# Relay_Driver_V1_1.net
KiCad netlist of a schematic drawn in EAGLE
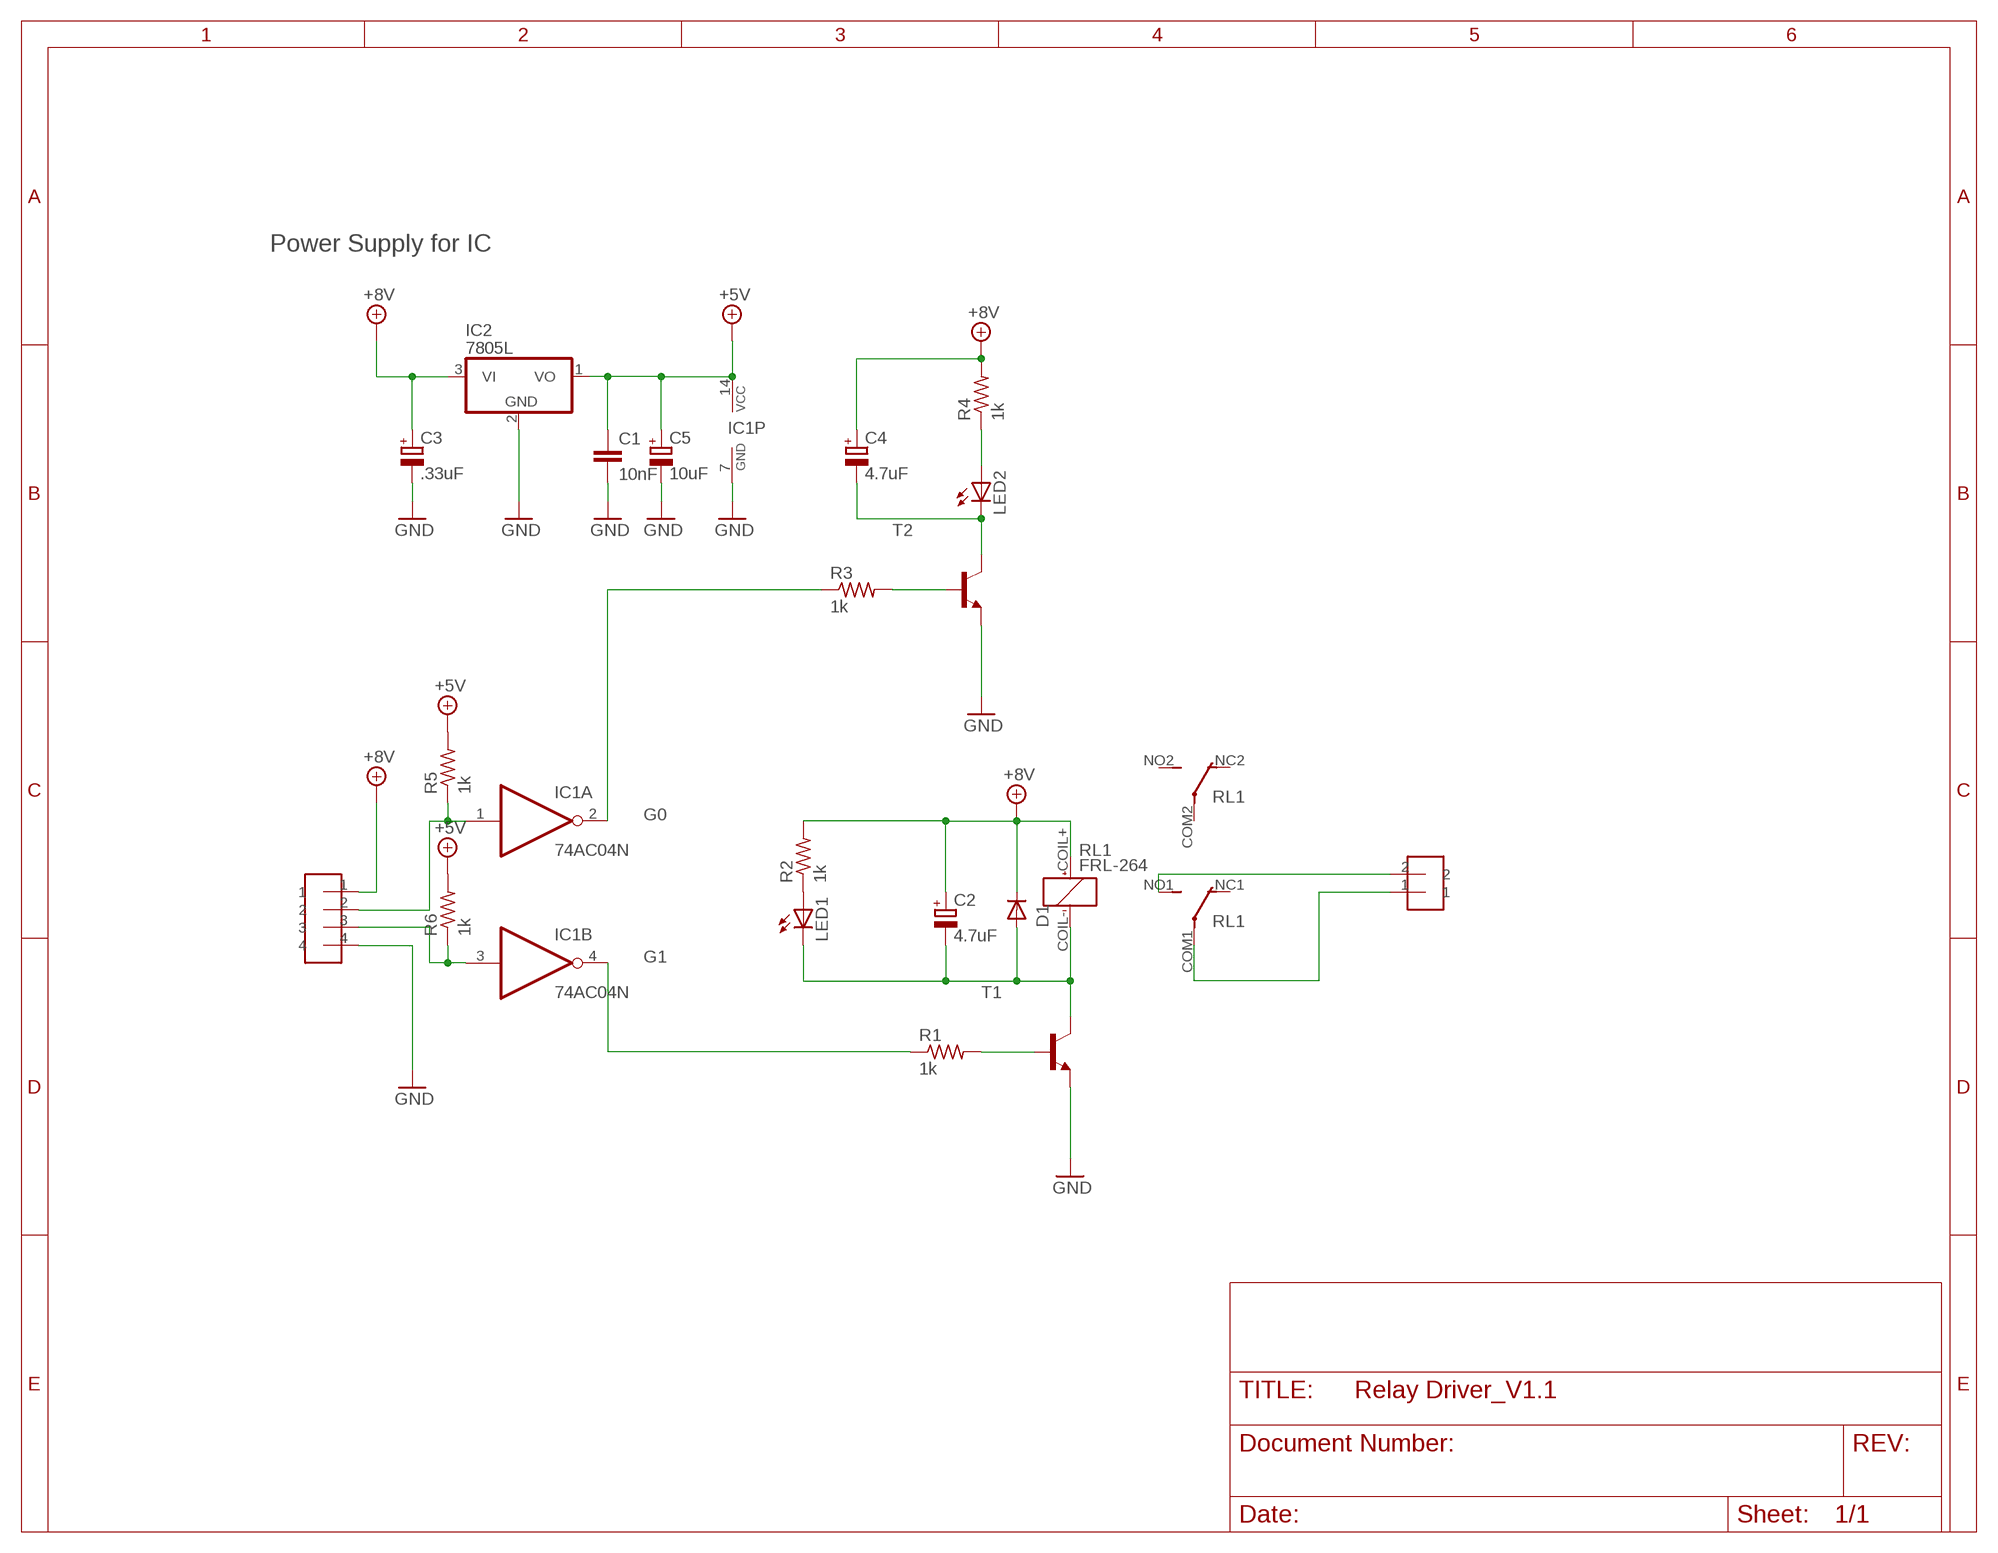
[diagram p0: schematic, sheet 1]

(export (version "E")
  (design (tool "Eeschema 10.0.6"))
  (components
    (comp (ref "C1")
      (value "10nF")
      (footprint "eagle-import:C075-042X103")
      (libsource (lib "eagle-import") (part "C-EU075-042X103"))
    )
    (comp (ref "C2")
      (value "4.7uF")
      (footprint "eagle-import:E3,5-10")
      (libsource (lib "eagle-import") (part "CPOL-EUE3.5-10"))
    )
    (comp (ref "C3")
      (value ".33uF")
      (footprint "eagle-import:E3,5-10")
      (libsource (lib "eagle-import") (part "CPOL-EUE3.5-10"))
    )
    (comp (ref "C4")
      (value "4.7uF")
      (footprint "eagle-import:E3,5-10")
      (libsource (lib "eagle-import") (part "CPOL-EUE3.5-10"))
    )
    (comp (ref "C5")
      (value "10uF")
      (footprint "eagle-import:E3,5-10")
      (libsource (lib "eagle-import") (part "CPOL-EUE3.5-10"))
    )
    (comp (ref "D1")
      (value "1N4148DO35-10")
      (footprint "eagle-import:DO35-10")
      (libsource (lib "eagle-import") (part "1N4148DO35-10"))
    )
    (comp (ref "IC1")
      (value "74AC04N")
      (footprint "eagle-import:DIL14")
      (libsource (lib "eagle-import") (part "7404NAC"))
    )
    (comp (ref "IC2")
      (value "7805L")
      (footprint "eagle-import:TO92")
      (libsource (lib "eagle-import") (part "78L05"))
    )
    (comp (ref "LED1")
      (value "LED5MM")
      (footprint "eagle-import:LED5MM")
      (libsource (lib "eagle-import") (part "LED5MM"))
    )
    (comp (ref "LED2")
      (value "LED5MM")
      (footprint "eagle-import:LED5MM")
      (libsource (lib "eagle-import") (part "LED5MM"))
    )
    (comp (ref "R1")
      (value "1k")
      (footprint "eagle-import:P0613V")
      (libsource (lib "eagle-import") (part "R-US_0613/5V"))
    )
    (comp (ref "R2")
      (value "1k")
      (footprint "eagle-import:P0613V")
      (libsource (lib "eagle-import") (part "R-US_0613/5V"))
    )
    (comp (ref "R3")
      (value "1k")
      (footprint "eagle-import:P0613V")
      (libsource (lib "eagle-import") (part "R-US_0613/5V"))
    )
    (comp (ref "R4")
      (value "1k")
      (footprint "eagle-import:P0613V")
      (libsource (lib "eagle-import") (part "R-US_0613/5V"))
    )
    (comp (ref "R5")
      (value "1k")
      (footprint "eagle-import:P0613V")
      (libsource (lib "eagle-import") (part "R-US_0613/5V"))
    )
    (comp (ref "R6")
      (value "1k")
      (footprint "eagle-import:P0613V")
      (libsource (lib "eagle-import") (part "R-US_0613/5V"))
    )
    (comp (ref "RL1")
      (value "FRL-264")
      (footprint "eagle-import:FRL-264")
      (libsource (lib "eagle-import") (part "FRL-264"))
    )
    (comp (ref "T1")
      (value "-NPN-TO92-EBC")
      (footprint "eagle-import:TO92-EBC")
      (libsource (lib "eagle-import") (part "-NPN-TO92-EBC"))
    )
    (comp (ref "T2")
      (value "-NPN-TO92-EBC")
      (footprint "eagle-import:TO92-EBC")
      (libsource (lib "eagle-import") (part "-NPN-TO92-EBC"))
    )
    (comp (ref "U$1")
      (value "1X4HEADER_100MIL")
      (footprint "eagle-import:1X4_100MIL")
      (libsource (lib "eagle-import") (part "1X4HEADER_100MIL"))
    )
    (comp (ref "U$2")
      (value "1X2HEADER_100MIL")
      (footprint "eagle-import:1X2_100MIL")
      (libsource (lib "eagle-import") (part "1X2HEADER_100MIL"))
    )
  )
  (nets
    (net (code "1") (name "+5V") (class "Default")
      (node (ref "C1") (pin "1") (pinfunction "1_1") (pintype "passive"))
      (node (ref "C5") (pin "+") (pinfunction "+_+") (pintype "passive"))
      (node (ref "IC1") (pin "14") (pinfunction "VCC_14") (pintype "power_in"))
      (node (ref "IC2") (pin "1") (pinfunction "VO_1") (pintype "passive"))
      (node (ref "R5") (pin "2") (pinfunction "2_2") (pintype "passive"))
      (node (ref "R6") (pin "2") (pinfunction "2_2") (pintype "passive"))
    )
    (net (code "2") (name "+8V") (class "Default")
      (node (ref "C2") (pin "+") (pinfunction "+_+") (pintype "passive"))
      (node (ref "C3") (pin "+") (pinfunction "+_+") (pintype "passive"))
      (node (ref "C4") (pin "+") (pinfunction "+_+") (pintype "passive"))
      (node (ref "D1") (pin "C") (pinfunction "C_C") (pintype "passive"))
      (node (ref "IC2") (pin "3") (pinfunction "VI_3") (pintype "input"))
      (node (ref "R2") (pin "2") (pinfunction "2_2") (pintype "passive"))
      (node (ref "R4") (pin "2") (pinfunction "2_2") (pintype "passive"))
      (node (ref "RL1") (pin "COIL+") (pinfunction "+_COIL+") (pintype "passive"))
      (node (ref "U$1") (pin "1") (pinfunction "1_1") (pintype "bidirectional"))
    )
    (net (code "3") (name "/G0") (class "Default")
      (node (ref "IC1") (pin "2") (pinfunction "O_2") (pintype "output"))
      (node (ref "R3") (pin "1") (pinfunction "1_1") (pintype "passive"))
    )
    (net (code "4") (name "/G1") (class "Default")
      (node (ref "IC1") (pin "4") (pinfunction "O_4") (pintype "output"))
      (node (ref "R1") (pin "1") (pinfunction "1_1") (pintype "passive"))
    )
    (net (code "5") (name "GND") (class "Default")
      (node (ref "C1") (pin "2") (pinfunction "2_2") (pintype "passive"))
      (node (ref "C3") (pin "-") (pinfunction "-_-") (pintype "passive"))
      (node (ref "C5") (pin "-") (pinfunction "-_-") (pintype "passive"))
      (node (ref "IC1") (pin "7") (pinfunction "GND_7") (pintype "power_in"))
      (node (ref "IC2") (pin "2") (pinfunction "GND_2") (pintype "passive"))
      (node (ref "T1") (pin "E") (pinfunction "E_E") (pintype "passive"))
      (node (ref "T2") (pin "E") (pinfunction "E_E") (pintype "passive"))
      (node (ref "U$1") (pin "4") (pinfunction "4_4") (pintype "bidirectional"))
    )
    (net (code "6") (name "Net-(IC1A-I)") (class "Default")
      (node (ref "IC1") (pin "1") (pinfunction "I_1") (pintype "input"))
      (node (ref "R5") (pin "1") (pinfunction "1_1") (pintype "passive"))
      (node (ref "U$1") (pin "2") (pinfunction "2_2") (pintype "bidirectional"))
    )
    (net (code "7") (name "Net-(IC1B-I)") (class "Default")
      (node (ref "IC1") (pin "3") (pinfunction "I_3") (pintype "input"))
      (node (ref "R6") (pin "1") (pinfunction "1_1") (pintype "passive"))
      (node (ref "U$1") (pin "3") (pinfunction "3_3") (pintype "bidirectional"))
    )
    (net (code "8") (name "Net-(LED1-C)") (class "Default")
      (node (ref "C2") (pin "-") (pinfunction "-_-") (pintype "passive"))
      (node (ref "D1") (pin "A") (pinfunction "A_A") (pintype "passive"))
      (node (ref "LED1") (pin "K") (pinfunction "C_K") (pintype "passive"))
      (node (ref "RL1") (pin "COIL-") (pinfunction "-_COIL-") (pintype "passive"))
      (node (ref "T1") (pin "C") (pinfunction "C_C") (pintype "passive"))
    )
    (net (code "9") (name "Net-(LED1-PadA)") (class "Default")
      (node (ref "LED1") (pin "A") (pinfunction "A_A") (pintype "passive"))
      (node (ref "R2") (pin "1") (pinfunction "1_1") (pintype "passive"))
    )
    (net (code "10") (name "Net-(LED2-C)") (class "Default")
      (node (ref "C4") (pin "-") (pinfunction "-_-") (pintype "passive"))
      (node (ref "LED2") (pin "K") (pinfunction "C_K") (pintype "passive"))
      (node (ref "T2") (pin "C") (pinfunction "C_C") (pintype "passive"))
    )
    (net (code "11") (name "Net-(LED2-PadA)") (class "Default")
      (node (ref "LED2") (pin "A") (pinfunction "A_A") (pintype "passive"))
      (node (ref "R4") (pin "1") (pinfunction "1_1") (pintype "passive"))
    )
    (net (code "12") (name "Net-(R1-Pad2)") (class "Default")
      (node (ref "R1") (pin "2") (pinfunction "2_2") (pintype "passive"))
      (node (ref "T1") (pin "B") (pinfunction "B_B") (pintype "passive"))
    )
    (net (code "13") (name "Net-(R3-Pad2)") (class "Default")
      (node (ref "R3") (pin "2") (pinfunction "2_2") (pintype "passive"))
      (node (ref "T2") (pin "B") (pinfunction "B_B") (pintype "passive"))
    )
    (net (code "14") (name "Net-(RL1B-P)") (class "Default")
      (node (ref "RL1") (pin "COM1") (pinfunction "P_COM1") (pintype "passive"))
      (node (ref "U$2") (pin "1") (pinfunction "1_1") (pintype "bidirectional"))
    )
    (net (code "15") (name "Net-(RL1B-S)") (class "Default")
      (node (ref "RL1") (pin "NO1") (pinfunction "S_NO1") (pintype "passive"))
      (node (ref "U$2") (pin "2") (pinfunction "2_2") (pintype "bidirectional"))
    )
    (net (code "16") (name "unconnected-(RL1B-O-PadNC1)") (class "Default")
      (node (ref "RL1") (pin "NC1") (pinfunction "O_NC1") (pintype "passive"))
    )
    (net (code "17") (name "unconnected-(RL1C-O-PadNC2)") (class "Default")
      (node (ref "RL1") (pin "NC2") (pinfunction "O_NC2") (pintype "passive"))
    )
    (net (code "18") (name "unconnected-(RL1C-P-PadCOM2)") (class "Default")
      (node (ref "RL1") (pin "COM2") (pinfunction "P_COM2") (pintype "passive"))
    )
    (net (code "19") (name "unconnected-(RL1C-S-PadNO2)") (class "Default")
      (node (ref "RL1") (pin "NO2") (pinfunction "S_NO2") (pintype "passive"))
    )
  )
)
